# Controller.net
KiCad netlist of a schematic drawn in EAGLE
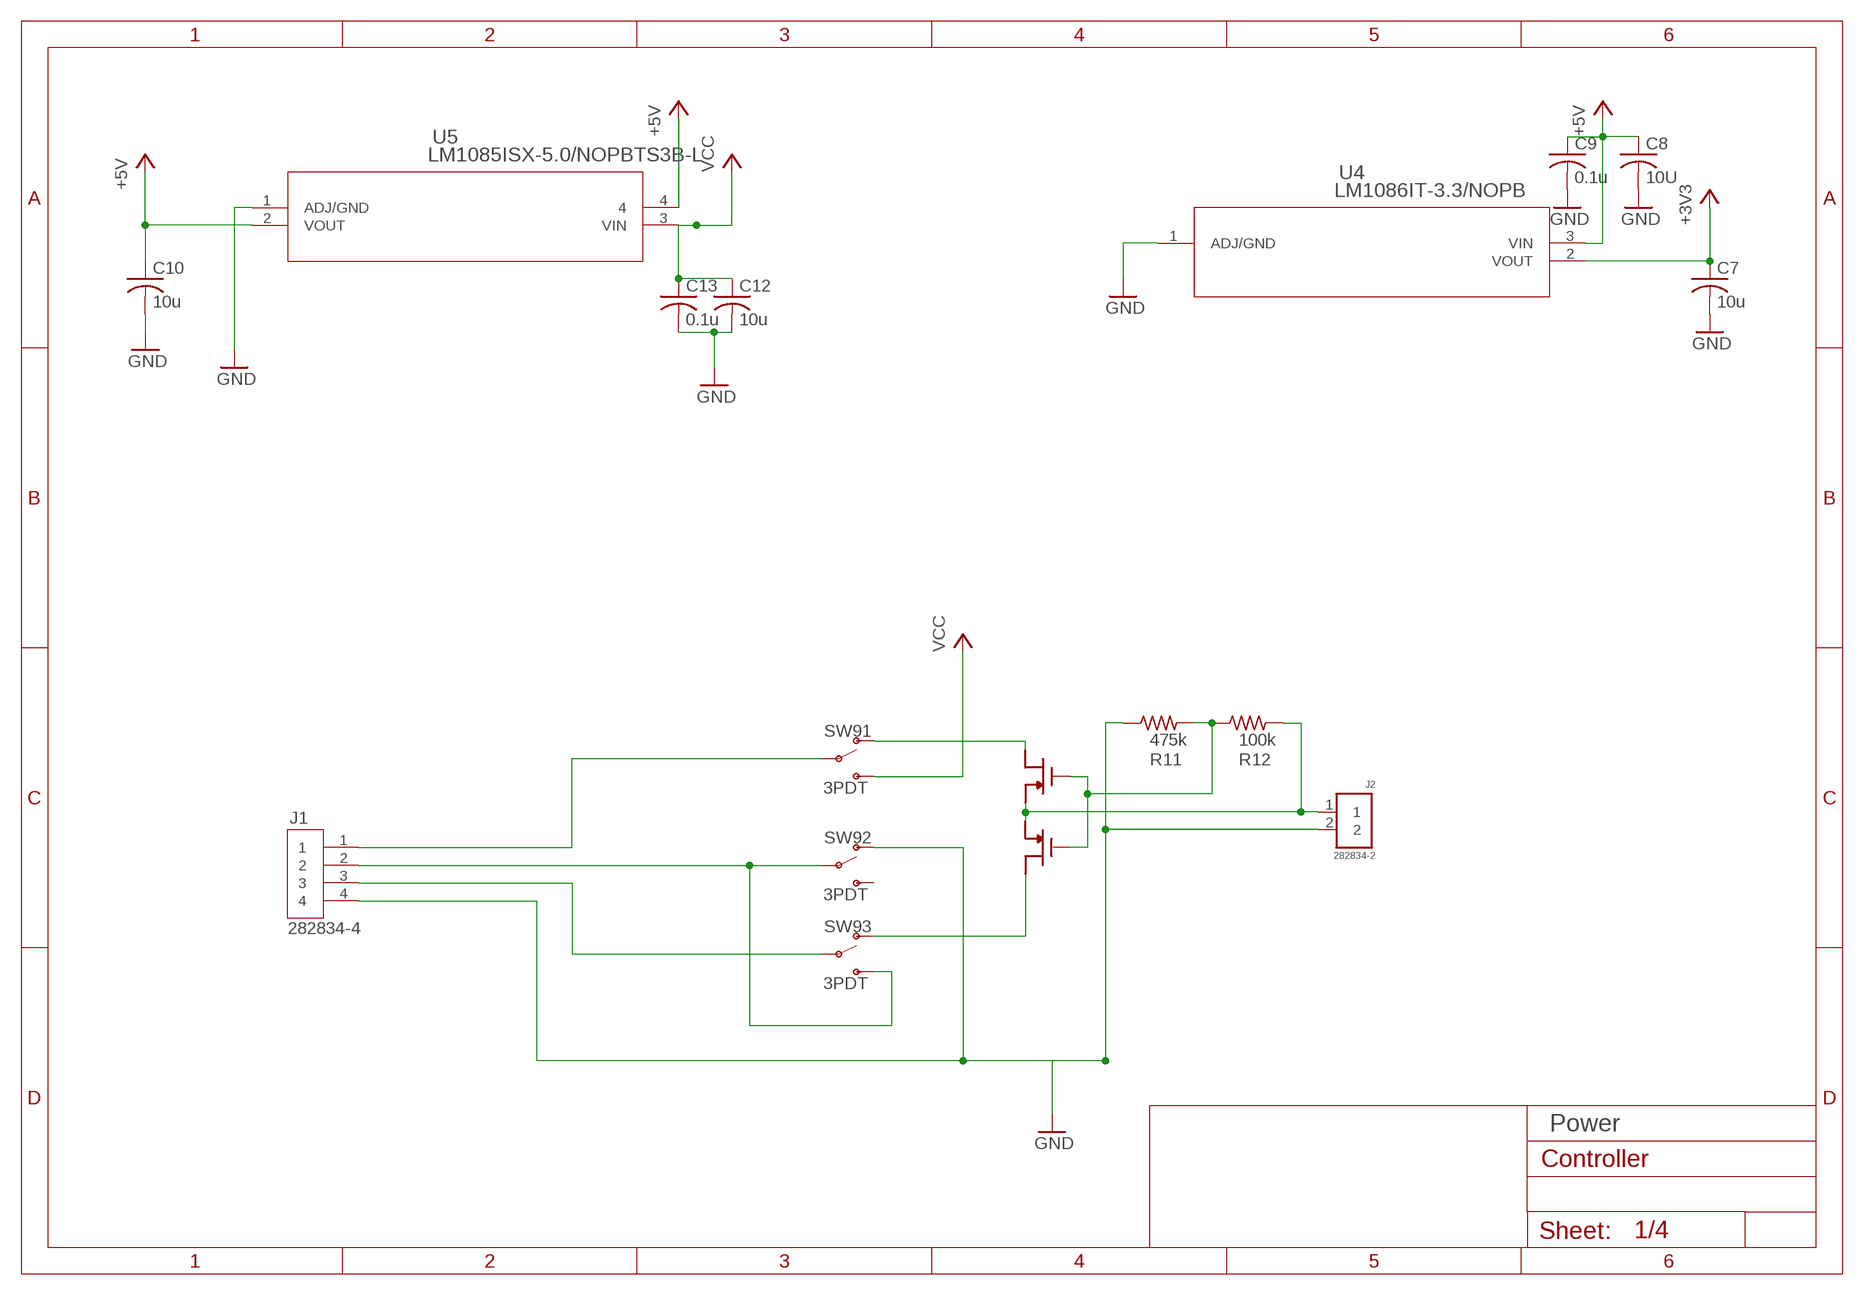
[diagram p0: schematic, sheet 1]
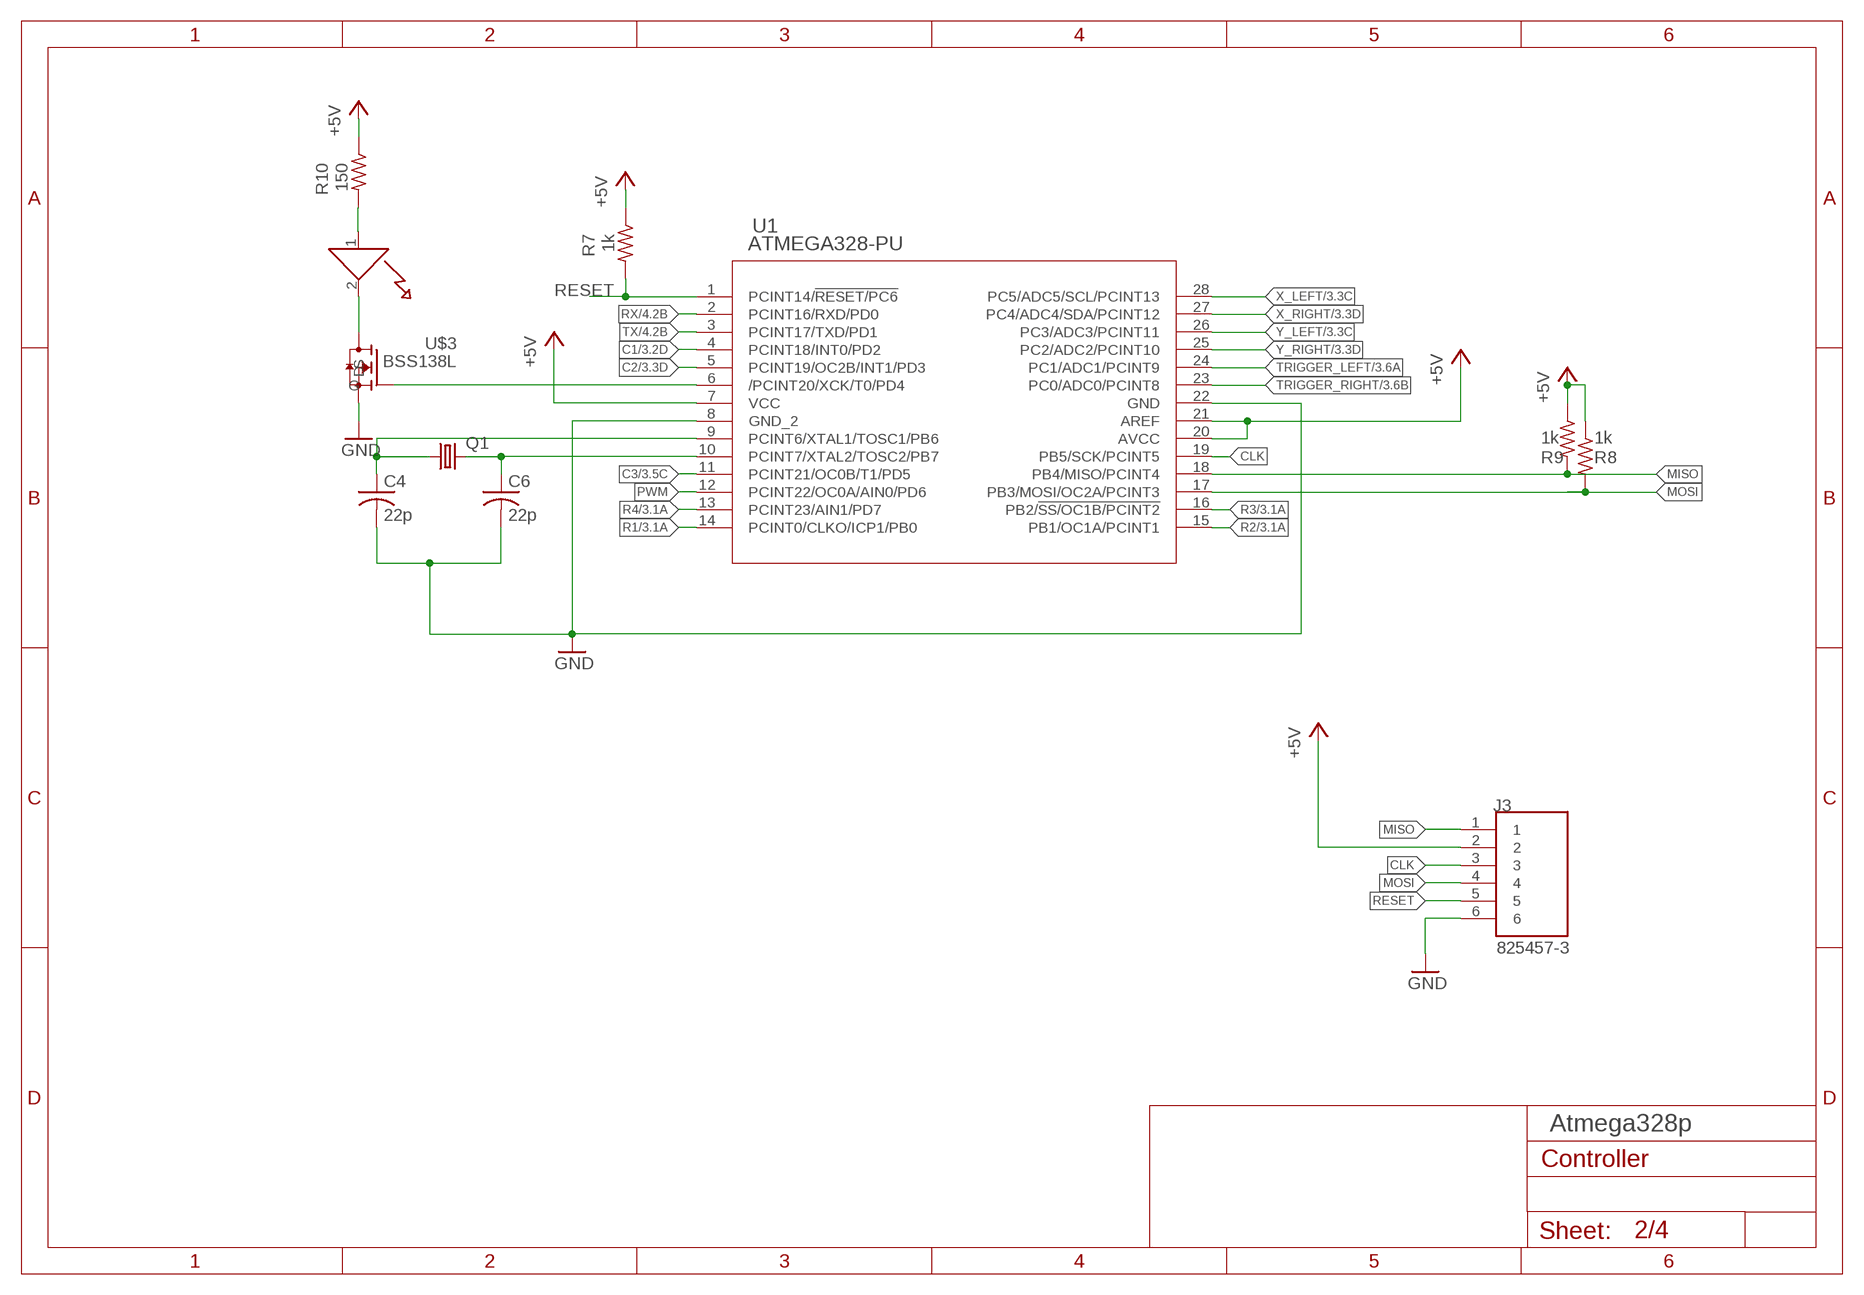
[diagram p1: schematic, sheet 2]
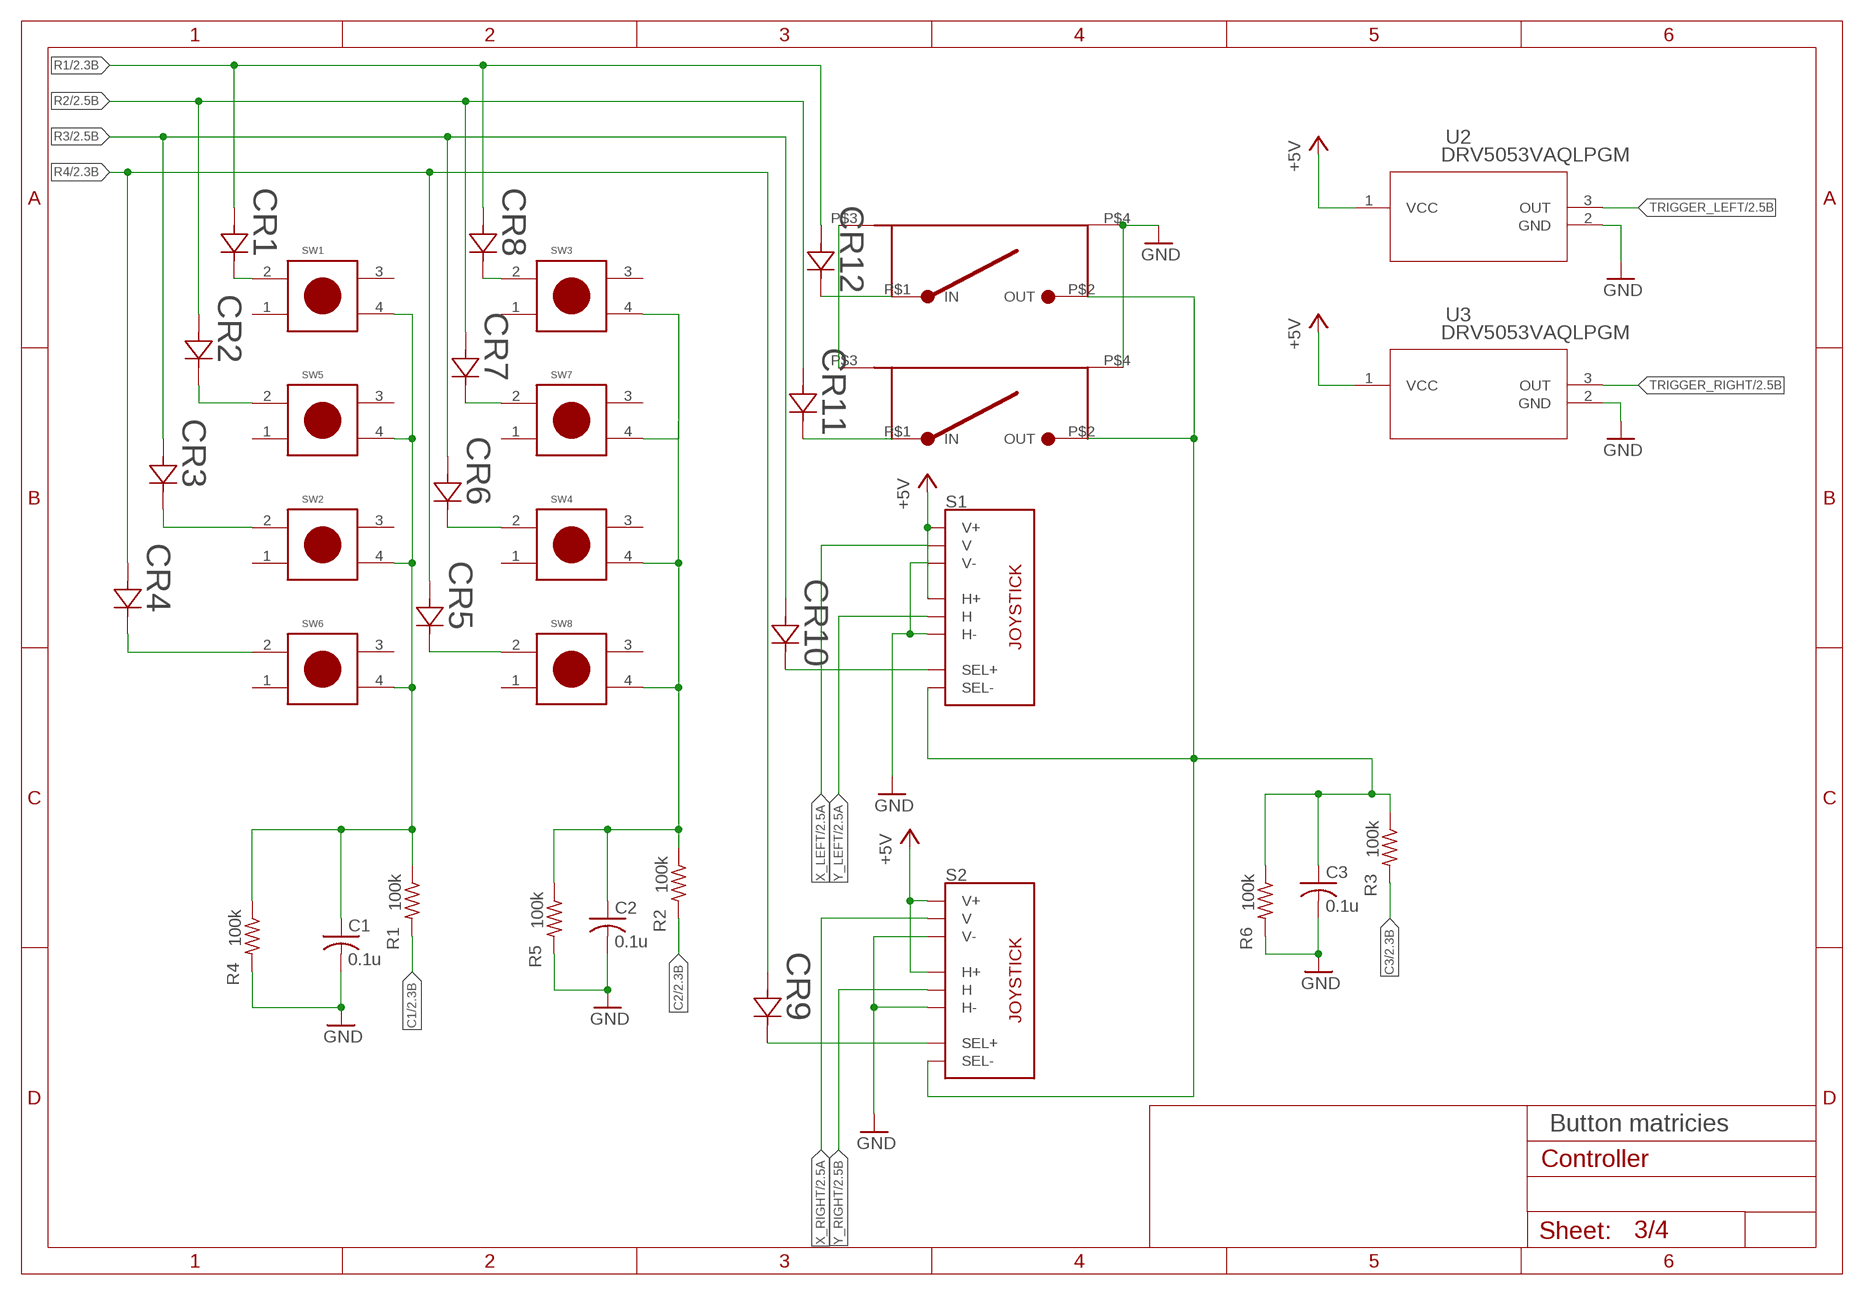
[diagram p2: schematic, sheet 3]
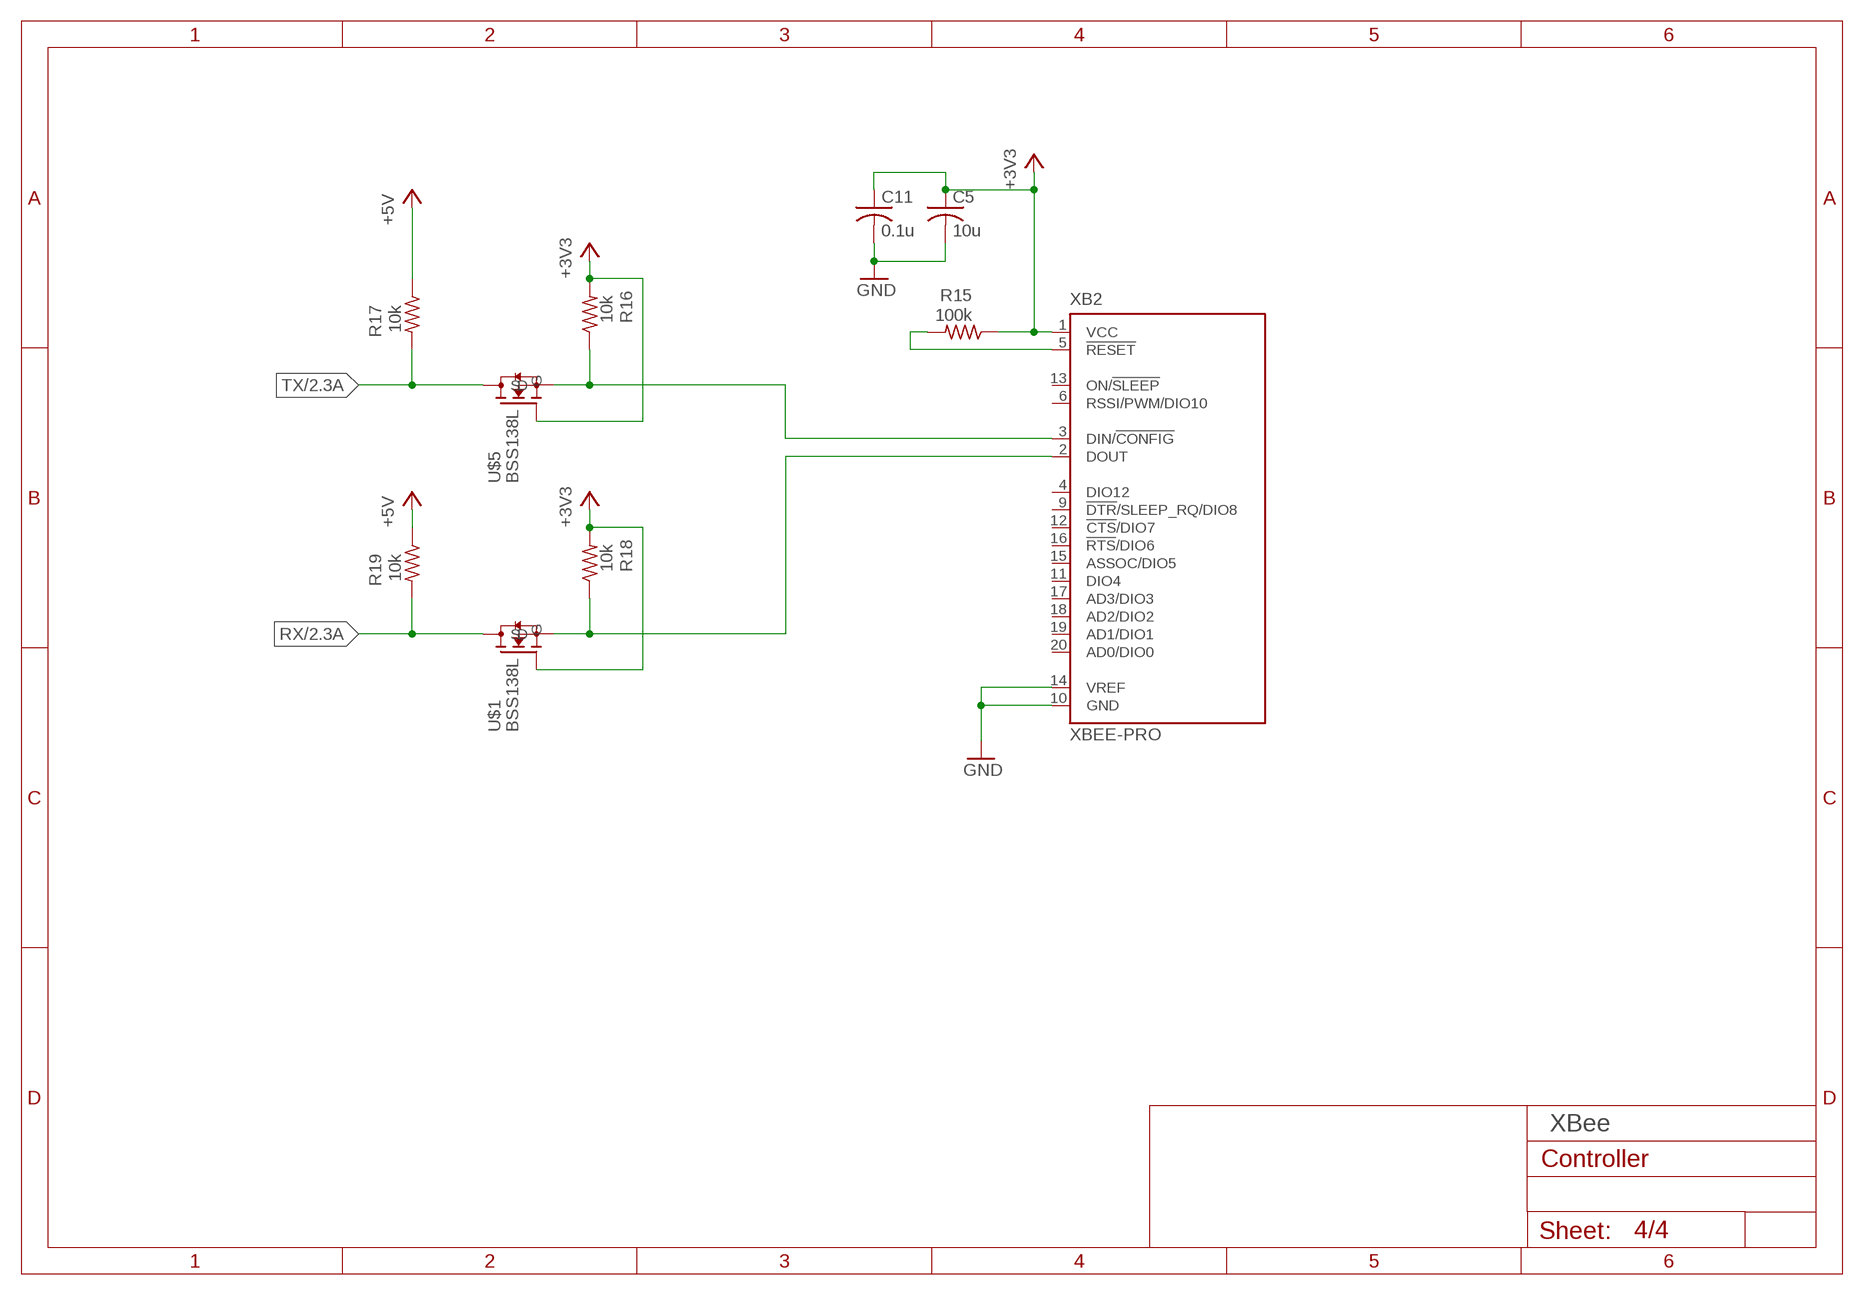
[diagram p3: schematic, sheet 4]

(export (version "E")
  (design (tool "Eeschema 10.0.6"))
  (components
    (comp (ref "C7")
      (value "10u")
      (footprint "eagle-import:C1206")
      (libsource (lib "eagle-import") (part "C-USC1206"))
    )
    (comp (ref "C8")
      (value "10U")
      (footprint "eagle-import:C1206")
      (libsource (lib "eagle-import") (part "C-USC1206"))
    )
    (comp (ref "C9")
      (value "0.1u")
      (footprint "eagle-import:C1206")
      (libsource (lib "eagle-import") (part "C-USC1206"))
    )
    (comp (ref "C10")
      (value "10u")
      (footprint "eagle-import:C1206")
      (libsource (lib "eagle-import") (part "C-USC1206"))
    )
    (comp (ref "C12")
      (value "10u")
      (footprint "eagle-import:C1206")
      (libsource (lib "eagle-import") (part "C-USC1206"))
    )
    (comp (ref "C13")
      (value "0.1u")
      (footprint "eagle-import:C1206")
      (libsource (lib "eagle-import") (part "C-USC1206"))
    )
    (comp (ref "J1")
      (value "282834-4")
      (footprint "eagle-import:HDRV4W85P254_4X1_1062X650X1000")
      (fields (field (name "DIGI-KEY_PART_NUMBER") "A98335-ND") (field (name "MF") "TE Connectivity"))
      (libsource (lib "eagle-import") (part "282834-4"))
    )
    (comp (ref "J2")
      (value "282834-2")
      (footprint "eagle-import:CONN_282834-2")
      (fields (field (name "DIGI-KEY_PART_NUMBER") "A98333-ND") (field (name "MF") "TE Connectivity"))
      (libsource (lib "eagle-import") (part "282834-2"))
    )
    (comp (ref "R11")
      (value "475k")
      (footprint "eagle-import:R1206")
      (libsource (lib "eagle-import") (part "R-US_R1206"))
    )
    (comp (ref "R12")
      (value "100k")
      (footprint "eagle-import:R1206")
      (libsource (lib "eagle-import") (part "R-US_R1206"))
    )
    (comp (ref "SW9")
      (value "3PDT")
      (footprint "eagle-import:3PDT")
      (fields (field (name "DIGIKEY_PART_NUMBER") "CWI359-ND"))
      (libsource (lib "eagle-import") (part "3PDT"))
    )
    (comp (ref "U4")
      (value "LM1086IT-3.3/NOPB")
      (footprint "eagle-import:T03B")
      (fields (field (name "MANUFACTURER_PART_NUMBER") "LM1086IT3.3NOPB"))
      (libsource (lib "eagle-import") (part "LM1086IT-3.3/NOPB"))
    )
    (comp (ref "U5")
      (value "LM1085ISX-5.0/NOPBTS3B-L")
      (footprint "eagle-import:TS3B-L")
      (fields (field (name "MANUFACTURER_PART_NUMBER") "LM1085ISX5.0NOPB"))
      (libsource (lib "eagle-import") (part "LM1085ISX-5.0/NOPBTS3B-L"))
    )
    (comp (ref "U6")
      (value "SSM6P40TULFCT-ND")
      (footprint "eagle-import:SMD6")
      (fields (field (name "DIGIKEY_PART_NUMBER") "SSM6P40TULFCT-ND "))
      (libsource (lib "eagle-import") (part "SSM6P40TULFCT-ND"))
    )
    (comp (ref "C4")
      (value "22p")
      (footprint "eagle-import:C1206")
      (libsource (lib "eagle-import") (part "C-USC1206"))
    )
    (comp (ref "C6")
      (value "22p")
      (footprint "eagle-import:C1206")
      (libsource (lib "eagle-import") (part "C-USC1206"))
    )
    (comp (ref "J3")
      (value "825457-3")
      (footprint "eagle-import:TE_825457-3")
      (fields (field (name "DIGI-KEY_PART_NUMBER") "A122907-ND") (field (name "MF") "TE Connectivity"))
      (libsource (lib "eagle-import") (part "825457-3"))
    )
    (comp (ref "Q1")
      (value "CRYSTALHC49S")
      (footprint "eagle-import:HC49_S")
      (libsource (lib "eagle-import") (part "CRYSTALHC49S"))
    )
    (comp (ref "R7")
      (value "1k")
      (footprint "eagle-import:R1206")
      (libsource (lib "eagle-import") (part "R-US_R1206"))
    )
    (comp (ref "R8")
      (value "1k")
      (footprint "eagle-import:R1206")
      (libsource (lib "eagle-import") (part "R-US_R1206"))
    )
    (comp (ref "R9")
      (value "1k")
      (footprint "eagle-import:R1206")
      (libsource (lib "eagle-import") (part "R-US_R1206"))
    )
    (comp (ref "R10")
      (value "150")
      (footprint "eagle-import:R1206")
      (libsource (lib "eagle-import") (part "R-US_R1206"))
    )
    (comp (ref "U$2")
      (value "LED")
      (footprint "eagle-import:R1206W")
      (libsource (lib "eagle-import") (part "LED"))
    )
    (comp (ref "U$3")
      (value "BSS138L")
      (footprint "eagle-import:BSS138L")
      (fields (field (name "DIGI-KEY_PART_NUMBER") "BSS138LCT-ND") (field (name "MF") "ON Semiconductor"))
      (libsource (lib "eagle-import") (part "BSS138L"))
    )
    (comp (ref "U1")
      (value "ATMEGA328-PU")
      (footprint "eagle-import:28P3")
      (fields (field (name "MANUFACTURER_PART_NUMBER") "ATMEGA328PU"))
      (libsource (lib "eagle-import") (part "ATMEGA328-PU"))
    )
    (comp (ref "C1")
      (value "0.1u")
      (footprint "eagle-import:C1206")
      (libsource (lib "eagle-import") (part "C-USC1206"))
    )
    (comp (ref "C2")
      (value "0.1u")
      (footprint "eagle-import:C1206")
      (libsource (lib "eagle-import") (part "C-USC1206"))
    )
    (comp (ref "C3")
      (value "0.1u")
      (footprint "eagle-import:C1206")
      (libsource (lib "eagle-import") (part "C-USC1206"))
    )
    (comp (ref "CR1")
      (value "MSS1P6-M3/89ADIODE_MSP3V3-M")
      (footprint "eagle-import:DIODE_MSP3V3-M")
      (fields (field (name "MANUFACTURER_PART_NUMBER") "MSS1P6M389A"))
      (libsource (lib "eagle-import") (part "MSS1P6-M3/89ADIODE_MSP3V3-M"))
    )
    (comp (ref "CR2")
      (value "MSS1P6-M3/89ADIODE_MSP3V3-M")
      (footprint "eagle-import:DIODE_MSP3V3-M")
      (fields (field (name "MANUFACTURER_PART_NUMBER") "MSS1P6M389A"))
      (libsource (lib "eagle-import") (part "MSS1P6-M3/89ADIODE_MSP3V3-M"))
    )
    (comp (ref "CR3")
      (value "MSS1P6-M3/89ADIODE_MSP3V3-M")
      (footprint "eagle-import:DIODE_MSP3V3-M")
      (fields (field (name "MANUFACTURER_PART_NUMBER") "MSS1P6M389A"))
      (libsource (lib "eagle-import") (part "MSS1P6-M3/89ADIODE_MSP3V3-M"))
    )
    (comp (ref "CR4")
      (value "MSS1P6-M3/89ADIODE_MSP3V3-M")
      (footprint "eagle-import:DIODE_MSP3V3-M")
      (fields (field (name "MANUFACTURER_PART_NUMBER") "MSS1P6M389A"))
      (libsource (lib "eagle-import") (part "MSS1P6-M3/89ADIODE_MSP3V3-M"))
    )
    (comp (ref "CR5")
      (value "MSS1P6-M3/89ADIODE_MSP3V3-M")
      (footprint "eagle-import:DIODE_MSP3V3-M")
      (fields (field (name "MANUFACTURER_PART_NUMBER") "MSS1P6M389A"))
      (libsource (lib "eagle-import") (part "MSS1P6-M3/89ADIODE_MSP3V3-M"))
    )
    (comp (ref "CR6")
      (value "MSS1P6-M3/89ADIODE_MSP3V3-M")
      (footprint "eagle-import:DIODE_MSP3V3-M")
      (fields (field (name "MANUFACTURER_PART_NUMBER") "MSS1P6M389A"))
      (libsource (lib "eagle-import") (part "MSS1P6-M3/89ADIODE_MSP3V3-M"))
    )
    (comp (ref "CR7")
      (value "MSS1P6-M3/89ADIODE_MSP3V3-M")
      (footprint "eagle-import:DIODE_MSP3V3-M")
      (fields (field (name "MANUFACTURER_PART_NUMBER") "MSS1P6M389A"))
      (libsource (lib "eagle-import") (part "MSS1P6-M3/89ADIODE_MSP3V3-M"))
    )
    (comp (ref "CR8")
      (value "MSS1P6-M3/89ADIODE_MSP3V3-M")
      (footprint "eagle-import:DIODE_MSP3V3-M")
      (fields (field (name "MANUFACTURER_PART_NUMBER") "MSS1P6M389A"))
      (libsource (lib "eagle-import") (part "MSS1P6-M3/89ADIODE_MSP3V3-M"))
    )
    (comp (ref "CR9")
      (value "MSS1P6-M3/89ADIODE_MSP3V3-M")
      (footprint "eagle-import:DIODE_MSP3V3-M")
      (fields (field (name "MANUFACTURER_PART_NUMBER") "MSS1P6M389A"))
      (libsource (lib "eagle-import") (part "MSS1P6-M3/89ADIODE_MSP3V3-M"))
    )
    (comp (ref "CR10")
      (value "MSS1P6-M3/89ADIODE_MSP3V3-M")
      (footprint "eagle-import:DIODE_MSP3V3-M")
      (fields (field (name "MANUFACTURER_PART_NUMBER") "MSS1P6M389A"))
      (libsource (lib "eagle-import") (part "MSS1P6-M3/89ADIODE_MSP3V3-M"))
    )
    (comp (ref "CR11")
      (value "MSS1P6-M3/89ADIODE_MSP3V3-M")
      (footprint "eagle-import:DIODE_MSP3V3-M")
      (fields (field (name "MANUFACTURER_PART_NUMBER") "MSS1P6M389A"))
      (libsource (lib "eagle-import") (part "MSS1P6-M3/89ADIODE_MSP3V3-M"))
    )
    (comp (ref "CR12")
      (value "MSS1P6-M3/89ADIODE_MSP3V3-M")
      (footprint "eagle-import:DIODE_MSP3V3-M")
      (fields (field (name "MANUFACTURER_PART_NUMBER") "MSS1P6M389A"))
      (libsource (lib "eagle-import") (part "MSS1P6-M3/89ADIODE_MSP3V3-M"))
    )
    (comp (ref "R1")
      (value "100k")
      (footprint "eagle-import:R1206")
      (libsource (lib "eagle-import") (part "R-US_R1206"))
    )
    (comp (ref "R2")
      (value "100k")
      (footprint "eagle-import:R1206")
      (libsource (lib "eagle-import") (part "R-US_R1206"))
    )
    (comp (ref "R3")
      (value "100k")
      (footprint "eagle-import:R1206")
      (libsource (lib "eagle-import") (part "R-US_R1206"))
    )
    (comp (ref "R4")
      (value "100k")
      (footprint "eagle-import:R1206")
      (libsource (lib "eagle-import") (part "R-US_R1206"))
    )
    (comp (ref "R5")
      (value "100k")
      (footprint "eagle-import:R1206")
      (libsource (lib "eagle-import") (part "R-US_R1206"))
    )
    (comp (ref "R6")
      (value "100k")
      (footprint "eagle-import:R1206")
      (libsource (lib "eagle-import") (part "R-US_R1206"))
    )
    (comp (ref "S1")
      (value "THUMBPOINTER-RKJXV1224005")
      (footprint "eagle-import:THUMBPOINTER-RKJXV1224005")
      (libsource (lib "eagle-import") (part "THUMBPOINTER-RKJXV1224005"))
    )
    (comp (ref "S2")
      (value "THUMBPOINTER-RKJXV1224005")
      (footprint "eagle-import:THUMBPOINTER-RKJXV1224005")
      (libsource (lib "eagle-import") (part "THUMBPOINTER-RKJXV1224005"))
    )
    (comp (ref "SW1")
      (value "MULTICOLOR_BUTTON")
      (footprint "eagle-import:PRT-14460")
      (fields (field (name "SPICEPREFIX") "S"))
      (libsource (lib "eagle-import") (part "MULTICOLOR_BUTTON"))
    )
    (comp (ref "SW2")
      (value "MULTICOLOR_BUTTON")
      (footprint "eagle-import:PRT-14460")
      (fields (field (name "SPICEPREFIX") "S"))
      (libsource (lib "eagle-import") (part "MULTICOLOR_BUTTON"))
    )
    (comp (ref "SW3")
      (value "MULTICOLOR_BUTTON")
      (footprint "eagle-import:PRT-14460")
      (fields (field (name "SPICEPREFIX") "S"))
      (libsource (lib "eagle-import") (part "MULTICOLOR_BUTTON"))
    )
    (comp (ref "SW4")
      (value "MULTICOLOR_BUTTON")
      (footprint "eagle-import:PRT-14460")
      (fields (field (name "SPICEPREFIX") "S"))
      (libsource (lib "eagle-import") (part "MULTICOLOR_BUTTON"))
    )
    (comp (ref "SW5")
      (value "MULTICOLOR_BUTTON")
      (footprint "eagle-import:PRT-14460")
      (fields (field (name "SPICEPREFIX") "S"))
      (libsource (lib "eagle-import") (part "MULTICOLOR_BUTTON"))
    )
    (comp (ref "SW6")
      (value "MULTICOLOR_BUTTON")
      (footprint "eagle-import:PRT-14460")
      (fields (field (name "SPICEPREFIX") "S"))
      (libsource (lib "eagle-import") (part "MULTICOLOR_BUTTON"))
    )
    (comp (ref "SW7")
      (value "MULTICOLOR_BUTTON")
      (footprint "eagle-import:PRT-14460")
      (fields (field (name "SPICEPREFIX") "S"))
      (libsource (lib "eagle-import") (part "MULTICOLOR_BUTTON"))
    )
    (comp (ref "SW8")
      (value "MULTICOLOR_BUTTON")
      (footprint "eagle-import:PRT-14460")
      (fields (field (name "SPICEPREFIX") "S"))
      (libsource (lib "eagle-import") (part "MULTICOLOR_BUTTON"))
    )
    (comp (ref "U$4")
      (value "BUMPER_BUMPER")
      (footprint "eagle-import:BUMPER_BUMPER")
      (libsource (lib "eagle-import") (part "BUMPER_BUMPER"))
    )
    (comp (ref "U$6")
      (value "BUMPER_BUMPER")
      (footprint "eagle-import:BUMPER_BUMPER")
      (libsource (lib "eagle-import") (part "BUMPER_BUMPER"))
    )
    (comp (ref "U2")
      (value "DRV5053VAQLPGM")
      (footprint "eagle-import:LPG3")
      (libsource (lib "eagle-import") (part "DRV5053VAQLPGM"))
    )
    (comp (ref "U3")
      (value "DRV5053VAQLPGM")
      (footprint "eagle-import:LPG3")
      (libsource (lib "eagle-import") (part "DRV5053VAQLPGM"))
    )
    (comp (ref "C5")
      (value "10u")
      (footprint "eagle-import:C1206")
      (libsource (lib "eagle-import") (part "C-USC1206"))
    )
    (comp (ref "C11")
      (value "0.1u")
      (footprint "eagle-import:C1206")
      (libsource (lib "eagle-import") (part "C-USC1206"))
    )
    (comp (ref "R15")
      (value "100k")
      (footprint "eagle-import:R1206")
      (libsource (lib "eagle-import") (part "R-US_R1206"))
    )
    (comp (ref "R16")
      (value "10k")
      (footprint "eagle-import:R1206")
      (libsource (lib "eagle-import") (part "R-US_R1206"))
    )
    (comp (ref "R17")
      (value "10k")
      (footprint "eagle-import:R1206")
      (libsource (lib "eagle-import") (part "R-US_R1206"))
    )
    (comp (ref "R18")
      (value "10k")
      (footprint "eagle-import:R1206")
      (libsource (lib "eagle-import") (part "R-US_R1206"))
    )
    (comp (ref "R19")
      (value "10k")
      (footprint "eagle-import:R1206")
      (libsource (lib "eagle-import") (part "R-US_R1206"))
    )
    (comp (ref "U$1")
      (value "BSS138L")
      (footprint "eagle-import:BSS138L")
      (fields (field (name "DIGI-KEY_PART_NUMBER") "BSS138LCT-ND") (field (name "MF") "ON Semiconductor"))
      (libsource (lib "eagle-import") (part "BSS138L"))
    )
    (comp (ref "U$5")
      (value "BSS138L")
      (footprint "eagle-import:BSS138L")
      (fields (field (name "DIGI-KEY_PART_NUMBER") "BSS138LCT-ND") (field (name "MF") "ON Semiconductor"))
      (libsource (lib "eagle-import") (part "BSS138L"))
    )
    (comp (ref "XB2")
      (value "XBEE-PRO")
      (footprint "eagle-import:XBEE-PRO")
      (fields (field (name "MPN") "XBP24-AWI-001"))
      (libsource (lib "eagle-import") (part "XBEE-PRO"))
    )
  )
  (nets
    (net (code "1") (name "+3V3") (class "Default")
      (node (ref "C11") (pin "1") (pinfunction "1_1") (pintype "passive"))
      (node (ref "C5") (pin "1") (pinfunction "1_1") (pintype "passive"))
      (node (ref "C7") (pin "1") (pinfunction "1_1") (pintype "passive"))
      (node (ref "R15") (pin "1") (pinfunction "1_1") (pintype "passive"))
      (node (ref "R16") (pin "2") (pinfunction "2_2") (pintype "passive"))
      (node (ref "R18") (pin "2") (pinfunction "2_2") (pintype "passive"))
      (node (ref "U$1") (pin "G") (pinfunction "G_G") (pintype "passive"))
      (node (ref "U$5") (pin "G") (pinfunction "G_G") (pintype "passive"))
      (node (ref "U4") (pin "2") (pinfunction "VOUT_2") (pintype "output"))
      (node (ref "XB2") (pin "1") (pinfunction "VCC_1") (pintype "power_in"))
    )
    (net (code "2") (name "+5V") (class "Default")
      (node (ref "C10") (pin "1") (pinfunction "1_1") (pintype "passive"))
      (node (ref "C8") (pin "1") (pinfunction "1_1") (pintype "passive"))
      (node (ref "C9") (pin "1") (pinfunction "1_1") (pintype "passive"))
      (node (ref "J3") (pin "2") (pinfunction "2_2") (pintype "passive"))
      (node (ref "R10") (pin "1") (pinfunction "1_1") (pintype "passive"))
      (node (ref "R17") (pin "1") (pinfunction "1_1") (pintype "passive"))
      (node (ref "R19") (pin "1") (pinfunction "1_1") (pintype "passive"))
      (node (ref "R7") (pin "1") (pinfunction "1_1") (pintype "passive"))
      (node (ref "R8") (pin "1") (pinfunction "1_1") (pintype "passive"))
      (node (ref "R9") (pin "1") (pinfunction "1_1") (pintype "passive"))
      (node (ref "S1") (pin "H1") (pinfunction "H+_H1") (pintype "bidirectional"))
      (node (ref "S1") (pin "V1") (pinfunction "V+_V1") (pintype "bidirectional"))
      (node (ref "S2") (pin "H1") (pinfunction "H+_H1") (pintype "bidirectional"))
      (node (ref "S2") (pin "V1") (pinfunction "V+_V1") (pintype "bidirectional"))
      (node (ref "U1") (pin "20") (pinfunction "AVCC_20") (pintype "power_in"))
      (node (ref "U1") (pin "21") (pinfunction "AREF_21") (pintype "power_in"))
      (node (ref "U1") (pin "7") (pinfunction "VCC_7") (pintype "power_in"))
      (node (ref "U2") (pin "1") (pinfunction "VCC_1") (pintype "power_in"))
      (node (ref "U3") (pin "1") (pinfunction "VCC_1") (pintype "power_in"))
      (node (ref "U4") (pin "3") (pinfunction "VIN_3") (pintype "input"))
      (node (ref "U5") (pin "2") (pinfunction "VOUT_2") (pintype "output"))
      (node (ref "U5") (pin "4") (pinfunction "4_4") (pintype "passive"))
    )
    (net (code "3") (name "C1") (class "Default")
      (node (ref "R1") (pin "2") (pinfunction "2_2") (pintype "passive"))
      (node (ref "U1") (pin "4") (pinfunction "PCINT18/INT0/PD2_4") (pintype "bidirectional"))
    )
    (net (code "4") (name "C2") (class "Default")
      (node (ref "R2") (pin "2") (pinfunction "2_2") (pintype "passive"))
      (node (ref "U1") (pin "5") (pinfunction "PCINT19/OC2B/INT1/PD3_5") (pintype "bidirectional"))
    )
    (net (code "5") (name "C3") (class "Default")
      (node (ref "R3") (pin "2") (pinfunction "2_2") (pintype "passive"))
      (node (ref "U1") (pin "11") (pinfunction "PCINT21/OC0B/T1/PD5_11") (pintype "bidirectional"))
    )
    (net (code "6") (name "CLK") (class "Default")
      (node (ref "J3") (pin "3") (pinfunction "3_3") (pintype "passive"))
      (node (ref "U1") (pin "19") (pinfunction "PB5/SCK/PCINT5_19") (pintype "bidirectional"))
    )
    (net (code "7") (name "GND") (class "Default")
      (node (ref "C1") (pin "2") (pinfunction "2_2") (pintype "passive"))
      (node (ref "C10") (pin "2") (pinfunction "2_2") (pintype "passive"))
      (node (ref "C11") (pin "2") (pinfunction "2_2") (pintype "passive"))
      (node (ref "C12") (pin "2") (pinfunction "2_2") (pintype "passive"))
      (node (ref "C13") (pin "2") (pinfunction "2_2") (pintype "passive"))
      (node (ref "C2") (pin "2") (pinfunction "2_2") (pintype "passive"))
      (node (ref "C3") (pin "2") (pinfunction "2_2") (pintype "passive"))
      (node (ref "C4") (pin "2") (pinfunction "2_2") (pintype "passive"))
      (node (ref "C5") (pin "2") (pinfunction "2_2") (pintype "passive"))
      (node (ref "C6") (pin "2") (pinfunction "2_2") (pintype "passive"))
      (node (ref "C7") (pin "2") (pinfunction "2_2") (pintype "passive"))
      (node (ref "C8") (pin "2") (pinfunction "2_2") (pintype "passive"))
      (node (ref "C9") (pin "2") (pinfunction "2_2") (pintype "passive"))
      (node (ref "J1") (pin "4") (pinfunction "4_4") (pintype "passive"))
      (node (ref "J2") (pin "2") (pinfunction "2_2") (pintype "passive"))
      (node (ref "J3") (pin "6") (pinfunction "6_6") (pintype "passive"))
      (node (ref "R11") (pin "1") (pinfunction "1_1") (pintype "passive"))
      (node (ref "R4") (pin "2") (pinfunction "2_2") (pintype "passive"))
      (node (ref "R5") (pin "2") (pinfunction "2_2") (pintype "passive"))
      (node (ref "R6") (pin "2") (pinfunction "2_2") (pintype "passive"))
      (node (ref "S1") (pin "H3") (pinfunction "H-_H3") (pintype "bidirectional"))
      (node (ref "S1") (pin "V3") (pinfunction "V-_V3") (pintype "bidirectional"))
      (node (ref "S2") (pin "H3") (pinfunction "H-_H3") (pintype "bidirectional"))
      (node (ref "S2") (pin "V3") (pinfunction "V-_V3") (pintype "bidirectional"))
      (node (ref "SW9") (pin "T21") (pinfunction "O_T21") (pintype "passive"))
      (node (ref "U$3") (pin "S") (pinfunction "S_S") (pintype "passive"))
      (node (ref "U$4") (pin "P$4") (pinfunction "GROUND_P$4") (pintype "bidirectional"))
      (node (ref "U$6") (pin "P$4") (pinfunction "GROUND_P$4") (pintype "bidirectional"))
      (node (ref "U1") (pin "22") (pinfunction "GND_22") (pintype "power_in"))
      (node (ref "U1") (pin "8") (pinfunction "GND_2_8") (pintype "power_in"))
      (node (ref "U2") (pin "2") (pinfunction "GND_2") (pintype "power_in"))
      (node (ref "U3") (pin "2") (pinfunction "GND_2") (pintype "power_in"))
      (node (ref "U4") (pin "1") (pinfunction "ADJ/GND_1") (pintype "passive"))
      (node (ref "U5") (pin "1") (pinfunction "ADJ/GND_1") (pintype "passive"))
      (node (ref "XB2") (pin "10") (pinfunction "GND_10") (pintype "power_in"))
      (node (ref "XB2") (pin "14") (pinfunction "VREF_14") (pintype "input"))
    )
    (net (code "8") (name "MISO") (class "Default")
      (node (ref "J3") (pin "1") (pinfunction "1_1") (pintype "passive"))
      (node (ref "R9") (pin "2") (pinfunction "2_2") (pintype "passive"))
      (node (ref "U1") (pin "18") (pinfunction "PB4/MISO/PCINT4_18") (pintype "bidirectional"))
    )
    (net (code "9") (name "MOSI") (class "Default")
      (node (ref "J3") (pin "4") (pinfunction "4_4") (pintype "passive"))
      (node (ref "R8") (pin "2") (pinfunction "2_2") (pintype "passive"))
      (node (ref "U1") (pin "17") (pinfunction "PB3/MOSI/OC2A/PCINT3_17") (pintype "bidirectional"))
    )
    (net (code "10") (name "N$C2") (class "Default")
      (node (ref "C2") (pin "1") (pinfunction "1_1") (pintype "passive"))
      (node (ref "R2") (pin "1") (pinfunction "1_1") (pintype "passive"))
      (node (ref "R5") (pin "1") (pinfunction "1_1") (pintype "passive"))
      (node (ref "SW3") (pin "4") (pinfunction "P$4_4") (pintype "bidirectional"))
      (node (ref "SW4") (pin "4") (pinfunction "P$4_4") (pintype "bidirectional"))
      (node (ref "SW7") (pin "4") (pinfunction "P$4_4") (pintype "bidirectional"))
      (node (ref "SW8") (pin "4") (pinfunction "P$4_4") (pintype "bidirectional"))
    )
    (net (code "11") (name "Net-(S1-SEL+)") (class "Default")
      (node (ref "CR10") (pin "1") (pinfunction "1_1") (pintype "passive"))
      (node (ref "S1") (pin "B1A") (pinfunction "SEL+_B1A") (pintype "bidirectional"))
    )
    (net (code "12") (name "Net-(S1-SEL-)") (class "Default")
      (node (ref "C3") (pin "1") (pinfunction "1_1") (pintype "passive"))
      (node (ref "R3") (pin "1") (pinfunction "1_1") (pintype "passive"))
      (node (ref "R6") (pin "1") (pinfunction "1_1") (pintype "passive"))
      (node (ref "S1") (pin "B2A") (pinfunction "SEL-_B2A") (pintype "bidirectional"))
      (node (ref "S2") (pin "B2A") (pinfunction "SEL-_B2A") (pintype "bidirectional"))
      (node (ref "U$4") (pin "P$2") (pinfunction "OUT_P$2") (pintype "bidirectional"))
      (node (ref "U$6") (pin "P$2") (pinfunction "OUT_P$2") (pintype "bidirectional"))
    )
    (net (code "13") (name "Net-(S2-SEL+)") (class "Default")
      (node (ref "CR9") (pin "1") (pinfunction "1_1") (pintype "passive"))
      (node (ref "S2") (pin "B1A") (pinfunction "SEL+_B1A") (pintype "bidirectional"))
    )
    (net (code "14") (name "Net-(SW1-P$1)") (class "Default")
      (node (ref "CR1") (pin "1") (pinfunction "1_1") (pintype "passive"))
      (node (ref "SW1") (pin "2") (pinfunction "P$1_2") (pintype "bidirectional"))
    )
    (net (code "15") (name "Net-(SW1-P$4)") (class "Default")
      (node (ref "C1") (pin "1") (pinfunction "1_1") (pintype "passive"))
      (node (ref "R1") (pin "1") (pinfunction "1_1") (pintype "passive"))
      (node (ref "R4") (pin "1") (pinfunction "1_1") (pintype "passive"))
      (node (ref "SW1") (pin "4") (pinfunction "P$4_4") (pintype "bidirectional"))
      (node (ref "SW2") (pin "4") (pinfunction "P$4_4") (pintype "bidirectional"))
      (node (ref "SW5") (pin "4") (pinfunction "P$4_4") (pintype "bidirectional"))
      (node (ref "SW6") (pin "4") (pinfunction "P$4_4") (pintype "bidirectional"))
    )
    (net (code "16") (name "Net-(SW2-P$1)") (class "Default")
      (node (ref "CR3") (pin "1") (pinfunction "1_1") (pintype "passive"))
      (node (ref "SW2") (pin "2") (pinfunction "P$1_2") (pintype "bidirectional"))
    )
    (net (code "17") (name "Net-(SW3-P$1)") (class "Default")
      (node (ref "CR8") (pin "1") (pinfunction "1_1") (pintype "passive"))
      (node (ref "SW3") (pin "2") (pinfunction "P$1_2") (pintype "bidirectional"))
    )
    (net (code "18") (name "Net-(SW4-P$1)") (class "Default")
      (node (ref "CR6") (pin "1") (pinfunction "1_1") (pintype "passive"))
      (node (ref "SW4") (pin "2") (pinfunction "P$1_2") (pintype "bidirectional"))
    )
    (net (code "19") (name "Net-(SW5-P$1)") (class "Default")
      (node (ref "CR2") (pin "1") (pinfunction "1_1") (pintype "passive"))
      (node (ref "SW5") (pin "2") (pinfunction "P$1_2") (pintype "bidirectional"))
    )
    (net (code "20") (name "Net-(SW6-P$1)") (class "Default")
      (node (ref "CR4") (pin "1") (pinfunction "1_1") (pintype "passive"))
      (node (ref "SW6") (pin "2") (pinfunction "P$1_2") (pintype "bidirectional"))
    )
    (net (code "21") (name "Net-(SW7-P$1)") (class "Default")
      (node (ref "CR7") (pin "1") (pinfunction "1_1") (pintype "passive"))
      (node (ref "SW7") (pin "2") (pinfunction "P$1_2") (pintype "bidirectional"))
    )
    (net (code "22") (name "Net-(SW8-P$1)") (class "Default")
      (node (ref "CR5") (pin "1") (pinfunction "1_1") (pintype "passive"))
      (node (ref "SW8") (pin "2") (pinfunction "P$1_2") (pintype "bidirectional"))
    )
    (net (code "23") (name "Net-(SW9A-O)") (class "Default")
      (node (ref "SW9") (pin "T11") (pinfunction "O_T11") (pintype "passive"))
      (node (ref "U6") (pin "P$6") (pinfunction "D_P$6") (pintype "bidirectional"))
    )
    (net (code "24") (name "Net-(SW9A-P)") (class "Default")
      (node (ref "J1") (pin "1") (pinfunction "1_1") (pintype "passive"))
      (node (ref "SW9") (pin "P1") (pinfunction "P_P1") (pintype "passive"))
    )
    (net (code "25") (name "Net-(SW9B-P)") (class "Default")
      (node (ref "J1") (pin "2") (pinfunction "2_2") (pintype "passive"))
      (node (ref "SW9") (pin "P2") (pinfunction "P_P2") (pintype "passive"))
      (node (ref "SW9") (pin "T32") (pinfunction "S_T32") (pintype "passive"))
    )
    (net (code "26") (name "Net-(SW9C-O)") (class "Default")
      (node (ref "SW9") (pin "T31") (pinfunction "O_T31") (pintype "passive"))
      (node (ref "U6") (pin "P$3") (pinfunction "D_P$3") (pintype "bidirectional"))
    )
    (net (code "27") (name "Net-(SW9C-P)") (class "Default")
      (node (ref "J1") (pin "3") (pinfunction "3_3") (pintype "passive"))
      (node (ref "SW9") (pin "P3") (pinfunction "P_P3") (pintype "passive"))
    )
    (net (code "28") (name "Net-(U$2-P$1)") (class "Default")
      (node (ref "R10") (pin "2") (pinfunction "2_2") (pintype "passive"))
      (node (ref "U$2") (pin "1") (pinfunction "P$1_1") (pintype "bidirectional"))
    )
    (net (code "29") (name "Net-(U$2-P$2)") (class "Default")
      (node (ref "U$2") (pin "2") (pinfunction "P$2_2") (pintype "bidirectional"))
      (node (ref "U$3") (pin "D") (pinfunction "D_D") (pintype "passive"))
    )
    (net (code "30") (name "Net-(U$4-GROUND1)") (class "Default")
      (node (ref "U$4") (pin "P$3") (pinfunction "GROUND1_P$3") (pintype "bidirectional"))
      (node (ref "U$6") (pin "P$3") (pinfunction "GROUND1_P$3") (pintype "bidirectional"))
    )
    (net (code "31") (name "Net-(U$4-IN)") (class "Default")
      (node (ref "CR12") (pin "1") (pinfunction "1_1") (pintype "passive"))
      (node (ref "U$4") (pin "P$1") (pinfunction "IN_P$1") (pintype "bidirectional"))
    )
    (net (code "32") (name "Net-(U$6-IN)") (class "Default")
      (node (ref "CR11") (pin "1") (pinfunction "1_1") (pintype "passive"))
      (node (ref "U$6") (pin "P$1") (pinfunction "IN_P$1") (pintype "bidirectional"))
    )
    (net (code "33") (name "Net-(U1-PCINT6{slash}XTAL1{slash}TOSC1{slash}PB6)") (class "Default")
      (node (ref "C4") (pin "1") (pinfunction "1_1") (pintype "passive"))
      (node (ref "Q1") (pin "1") (pinfunction "1_1") (pintype "passive"))
      (node (ref "U1") (pin "9") (pinfunction "PCINT6/XTAL1/TOSC1/PB6_9") (pintype "bidirectional"))
    )
    (net (code "34") (name "Net-(U1-PCINT7{slash}XTAL2{slash}TOSC2{slash}PB7)") (class "Default")
      (node (ref "C6") (pin "1") (pinfunction "1_1") (pintype "passive"))
      (node (ref "Q1") (pin "2") (pinfunction "2_2") (pintype "passive"))
      (node (ref "U1") (pin "10") (pinfunction "PCINT7/XTAL2/TOSC2/PB7_10") (pintype "bidirectional"))
    )
    (net (code "35") (name "Net-(U1-{slash}PCINT20{slash}XCK{slash}T0{slash}PD4)") (class "Default")
      (node (ref "U$3") (pin "G") (pinfunction "G_G") (pintype "passive"))
      (node (ref "U1") (pin "6") (pinfunction "/PCINT20/XCK/T0/PD4_6") (pintype "bidirectional"))
    )
    (net (code "36") (name "Net-(U6A-G)") (class "Default")
      (node (ref "R11") (pin "2") (pinfunction "2_2") (pintype "passive"))
      (node (ref "R12") (pin "1") (pinfunction "1_1") (pintype "passive"))
      (node (ref "U6") (pin "P$2") (pinfunction "G_P$2") (pintype "bidirectional"))
      (node (ref "U6") (pin "P$5") (pinfunction "G_P$5") (pintype "bidirectional"))
    )
    (net (code "37") (name "Net-(U6A-S)") (class "Default")
      (node (ref "J2") (pin "1") (pinfunction "1_1") (pintype "passive"))
      (node (ref "R12") (pin "2") (pinfunction "2_2") (pintype "passive"))
      (node (ref "U6") (pin "P$1") (pinfunction "S_P$1") (pintype "bidirectional"))
      (node (ref "U6") (pin "P$4") (pinfunction "S_P$4") (pintype "bidirectional"))
    )
    (net (code "38") (name "Net-(XB2-DIN{slash}~{CONFIG})") (class "Default")
      (node (ref "R16") (pin "1") (pinfunction "1_1") (pintype "passive"))
      (node (ref "U$5") (pin "S") (pinfunction "S_S") (pintype "passive"))
      (node (ref "XB2") (pin "3") (pinfunction "DIN/~{CONFIG}_3") (pintype "input"))
    )
    (net (code "39") (name "Net-(XB2-DOUT)") (class "Default")
      (node (ref "R18") (pin "1") (pinfunction "1_1") (pintype "passive"))
      (node (ref "U$1") (pin "S") (pinfunction "S_S") (pintype "passive"))
      (node (ref "XB2") (pin "2") (pinfunction "DOUT_2") (pintype "output"))
    )
    (net (code "40") (name "Net-(XB2-~{RESET})") (class "Default")
      (node (ref "R15") (pin "2") (pinfunction "2_2") (pintype "passive"))
      (node (ref "XB2") (pin "5") (pinfunction "~{RESET}_5") (pintype "input"))
    )
    (net (code "41") (name "PWM") (class "Default")
      (node (ref "U1") (pin "12") (pinfunction "PCINT22/OC0A/AIN0/PD6_12") (pintype "bidirectional"))
    )
    (net (code "42") (name "R1") (class "Default")
      (node (ref "CR1") (pin "2") (pinfunction "2_2") (pintype "passive"))
      (node (ref "CR12") (pin "2") (pinfunction "2_2") (pintype "passive"))
      (node (ref "CR8") (pin "2") (pinfunction "2_2") (pintype "passive"))
      (node (ref "U1") (pin "14") (pinfunction "PCINT0/CLKO/ICP1/PB0_14") (pintype "bidirectional"))
    )
    (net (code "43") (name "R2") (class "Default")
      (node (ref "CR11") (pin "2") (pinfunction "2_2") (pintype "passive"))
      (node (ref "CR2") (pin "2") (pinfunction "2_2") (pintype "passive"))
      (node (ref "CR7") (pin "2") (pinfunction "2_2") (pintype "passive"))
      (node (ref "U1") (pin "15") (pinfunction "PB1/OC1A/PCINT1_15") (pintype "bidirectional"))
    )
    (net (code "44") (name "R3") (class "Default")
      (node (ref "CR10") (pin "2") (pinfunction "2_2") (pintype "passive"))
      (node (ref "CR3") (pin "2") (pinfunction "2_2") (pintype "passive"))
      (node (ref "CR6") (pin "2") (pinfunction "2_2") (pintype "passive"))
      (node (ref "U1") (pin "16") (pinfunction "PB2/~{SS/OC1B/PCINT2}_16") (pintype "bidirectional"))
    )
    (net (code "45") (name "R4") (class "Default")
      (node (ref "CR4") (pin "2") (pinfunction "2_2") (pintype "passive"))
      (node (ref "CR5") (pin "2") (pinfunction "2_2") (pintype "passive"))
      (node (ref "CR9") (pin "2") (pinfunction "2_2") (pintype "passive"))
      (node (ref "U1") (pin "13") (pinfunction "PCINT23/AIN1/PD7_13") (pintype "bidirectional"))
    )
    (net (code "46") (name "RESET") (class "Default")
      (node (ref "J3") (pin "5") (pinfunction "5_5") (pintype "passive"))
      (node (ref "R7") (pin "2") (pinfunction "2_2") (pintype "passive"))
      (node (ref "U1") (pin "1") (pinfunction "PCINT14/~{RESET/PC6}_1") (pintype "bidirectional"))
    )
    (net (code "47") (name "RX") (class "Default")
      (node (ref "R19") (pin "2") (pinfunction "2_2") (pintype "passive"))
      (node (ref "U$1") (pin "D") (pinfunction "D_D") (pintype "passive"))
      (node (ref "U1") (pin "2") (pinfunction "PCINT16/RXD/PD0_2") (pintype "bidirectional"))
    )
    (net (code "48") (name "TRIGGER_LEFT") (class "Default")
      (node (ref "U1") (pin "24") (pinfunction "PC1/ADC1/PCINT9_24") (pintype "bidirectional"))
      (node (ref "U2") (pin "3") (pinfunction "OUT_3") (pintype "output"))
    )
    (net (code "49") (name "TRIGGER_RIGHT") (class "Default")
      (node (ref "U1") (pin "23") (pinfunction "PC0/ADC0/PCINT8_23") (pintype "bidirectional"))
      (node (ref "U3") (pin "3") (pinfunction "OUT_3") (pintype "output"))
    )
    (net (code "50") (name "TX") (class "Default")
      (node (ref "R17") (pin "2") (pinfunction "2_2") (pintype "passive"))
      (node (ref "U$5") (pin "D") (pinfunction "D_D") (pintype "passive"))
      (node (ref "U1") (pin "3") (pinfunction "PCINT17/TXD/PD1_3") (pintype "bidirectional"))
    )
    (net (code "51") (name "VCC") (class "Default")
      (node (ref "C12") (pin "1") (pinfunction "1_1") (pintype "passive"))
      (node (ref "C13") (pin "1") (pinfunction "1_1") (pintype "passive"))
      (node (ref "SW9") (pin "T12") (pinfunction "S_T12") (pintype "passive"))
      (node (ref "U5") (pin "3") (pinfunction "VIN_3") (pintype "input"))
    )
    (net (code "52") (name "X_LEFT") (class "Default")
      (node (ref "S1") (pin "V2") (pinfunction "V_V2") (pintype "bidirectional"))
      (node (ref "U1") (pin "28") (pinfunction "PC5/ADC5/SCL/PCINT13_28") (pintype "bidirectional"))
    )
    (net (code "53") (name "X_RIGHT") (class "Default")
      (node (ref "S2") (pin "V2") (pinfunction "V_V2") (pintype "bidirectional"))
      (node (ref "U1") (pin "27") (pinfunction "PC4/ADC4/SDA/PCINT12_27") (pintype "bidirectional"))
    )
    (net (code "54") (name "Y_LEFT") (class "Default")
      (node (ref "S1") (pin "H2") (pinfunction "H_H2") (pintype "bidirectional"))
      (node (ref "U1") (pin "26") (pinfunction "PC3/ADC3/PCINT11_26") (pintype "bidirectional"))
    )
    (net (code "55") (name "Y_RIGHT") (class "Default")
      (node (ref "S2") (pin "H2") (pinfunction "H_H2") (pintype "bidirectional"))
      (node (ref "U1") (pin "25") (pinfunction "PC2/ADC2/PCINT10_25") (pintype "bidirectional"))
    )
    (net (code "56") (name "unconnected-(SW1-P$2-Pad1)") (class "Default")
      (node (ref "SW1") (pin "1") (pinfunction "P$2_1") (pintype "bidirectional"))
    )
    (net (code "57") (name "unconnected-(SW1-P$3-Pad3)") (class "Default")
      (node (ref "SW1") (pin "3") (pinfunction "P$3_3") (pintype "bidirectional"))
    )
    (net (code "58") (name "unconnected-(SW2-P$2-Pad1)") (class "Default")
      (node (ref "SW2") (pin "1") (pinfunction "P$2_1") (pintype "bidirectional"))
    )
    (net (code "59") (name "unconnected-(SW2-P$3-Pad3)") (class "Default")
      (node (ref "SW2") (pin "3") (pinfunction "P$3_3") (pintype "bidirectional"))
    )
    (net (code "60") (name "unconnected-(SW3-P$2-Pad1)") (class "Default")
      (node (ref "SW3") (pin "1") (pinfunction "P$2_1") (pintype "bidirectional"))
    )
    (net (code "61") (name "unconnected-(SW3-P$3-Pad3)") (class "Default")
      (node (ref "SW3") (pin "3") (pinfunction "P$3_3") (pintype "bidirectional"))
    )
    (net (code "62") (name "unconnected-(SW4-P$2-Pad1)") (class "Default")
      (node (ref "SW4") (pin "1") (pinfunction "P$2_1") (pintype "bidirectional"))
    )
    (net (code "63") (name "unconnected-(SW4-P$3-Pad3)") (class "Default")
      (node (ref "SW4") (pin "3") (pinfunction "P$3_3") (pintype "bidirectional"))
    )
    (net (code "64") (name "unconnected-(SW5-P$2-Pad1)") (class "Default")
      (node (ref "SW5") (pin "1") (pinfunction "P$2_1") (pintype "bidirectional"))
    )
    (net (code "65") (name "unconnected-(SW5-P$3-Pad3)") (class "Default")
      (node (ref "SW5") (pin "3") (pinfunction "P$3_3") (pintype "bidirectional"))
    )
    (net (code "66") (name "unconnected-(SW6-P$2-Pad1)") (class "Default")
      (node (ref "SW6") (pin "1") (pinfunction "P$2_1") (pintype "bidirectional"))
    )
    (net (code "67") (name "unconnected-(SW6-P$3-Pad3)") (class "Default")
      (node (ref "SW6") (pin "3") (pinfunction "P$3_3") (pintype "bidirectional"))
    )
    (net (code "68") (name "unconnected-(SW7-P$2-Pad1)") (class "Default")
      (node (ref "SW7") (pin "1") (pinfunction "P$2_1") (pintype "bidirectional"))
    )
    (net (code "69") (name "unconnected-(SW7-P$3-Pad3)") (class "Default")
      (node (ref "SW7") (pin "3") (pinfunction "P$3_3") (pintype "bidirectional"))
    )
    (net (code "70") (name "unconnected-(SW8-P$2-Pad1)") (class "Default")
      (node (ref "SW8") (pin "1") (pinfunction "P$2_1") (pintype "bidirectional"))
    )
    (net (code "71") (name "unconnected-(SW8-P$3-Pad3)") (class "Default")
      (node (ref "SW8") (pin "3") (pinfunction "P$3_3") (pintype "bidirectional"))
    )
    (net (code "72") (name "unconnected-(SW9B-S-PadT22)") (class "Default")
      (node (ref "SW9") (pin "T22") (pinfunction "S_T22") (pintype "passive"))
    )
    (net (code "73") (name "unconnected-(XB2-AD0{slash}DIO0-Pad20)") (class "Default")
      (node (ref "XB2") (pin "20") (pinfunction "AD0/DIO0_20") (pintype "bidirectional"))
    )
    (net (code "74") (name "unconnected-(XB2-AD1{slash}DIO1-Pad19)") (class "Default")
      (node (ref "XB2") (pin "19") (pinfunction "AD1/DIO1_19") (pintype "bidirectional"))
    )
    (net (code "75") (name "unconnected-(XB2-AD2{slash}DIO2-Pad18)") (class "Default")
      (node (ref "XB2") (pin "18") (pinfunction "AD2/DIO2_18") (pintype "bidirectional"))
    )
    (net (code "76") (name "unconnected-(XB2-AD3{slash}DIO3-Pad17)") (class "Default")
      (node (ref "XB2") (pin "17") (pinfunction "AD3/DIO3_17") (pintype "bidirectional"))
    )
    (net (code "77") (name "unconnected-(XB2-ASSOC{slash}DIO5-Pad15)") (class "Default")
      (node (ref "XB2") (pin "15") (pinfunction "ASSOC/DIO5_15") (pintype "bidirectional"))
    )
    (net (code "78") (name "unconnected-(XB2-DIO4-Pad11)") (class "Default")
      (node (ref "XB2") (pin "11") (pinfunction "DIO4_11") (pintype "bidirectional"))
    )
    (net (code "79") (name "unconnected-(XB2-DIO12-Pad4)") (class "Default")
      (node (ref "XB2") (pin "4") (pinfunction "DIO12_4") (pintype "bidirectional"))
    )
    (net (code "80") (name "unconnected-(XB2-ON{slash}~{SLEEP}-Pad13)") (class "Default")
      (node (ref "XB2") (pin "13") (pinfunction "ON/~{SLEEP}_13") (pintype "output"))
    )
    (net (code "81") (name "unconnected-(XB2-RSSI{slash}PWM{slash}DIO10-Pad6)") (class "Default")
      (node (ref "XB2") (pin "6") (pinfunction "RSSI/PWM/DIO10_6") (pintype "output"))
    )
    (net (code "82") (name "unconnected-(XB2-~{CTS}{slash}DIO7-Pad12)") (class "Default")
      (node (ref "XB2") (pin "12") (pinfunction "~{CTS}/DIO7_12") (pintype "bidirectional"))
    )
    (net (code "83") (name "unconnected-(XB2-~{DTR}{slash}SLEEP_RQ{slash}DIO8-Pad9)") (class "Default")
      (node (ref "XB2") (pin "9") (pinfunction "~{DTR}/SLEEP_RQ/DIO8_9") (pintype "bidirectional"))
    )
    (net (code "84") (name "unconnected-(XB2-~{RTS}{slash}DIO6-Pad16)") (class "Default")
      (node (ref "XB2") (pin "16") (pinfunction "~{RTS}/DIO6_16") (pintype "bidirectional"))
    )
  )
)
